# ESP32-Proto2-OSHPARK_Rev2.net
KiCad netlist of a schematic drawn in EAGLE
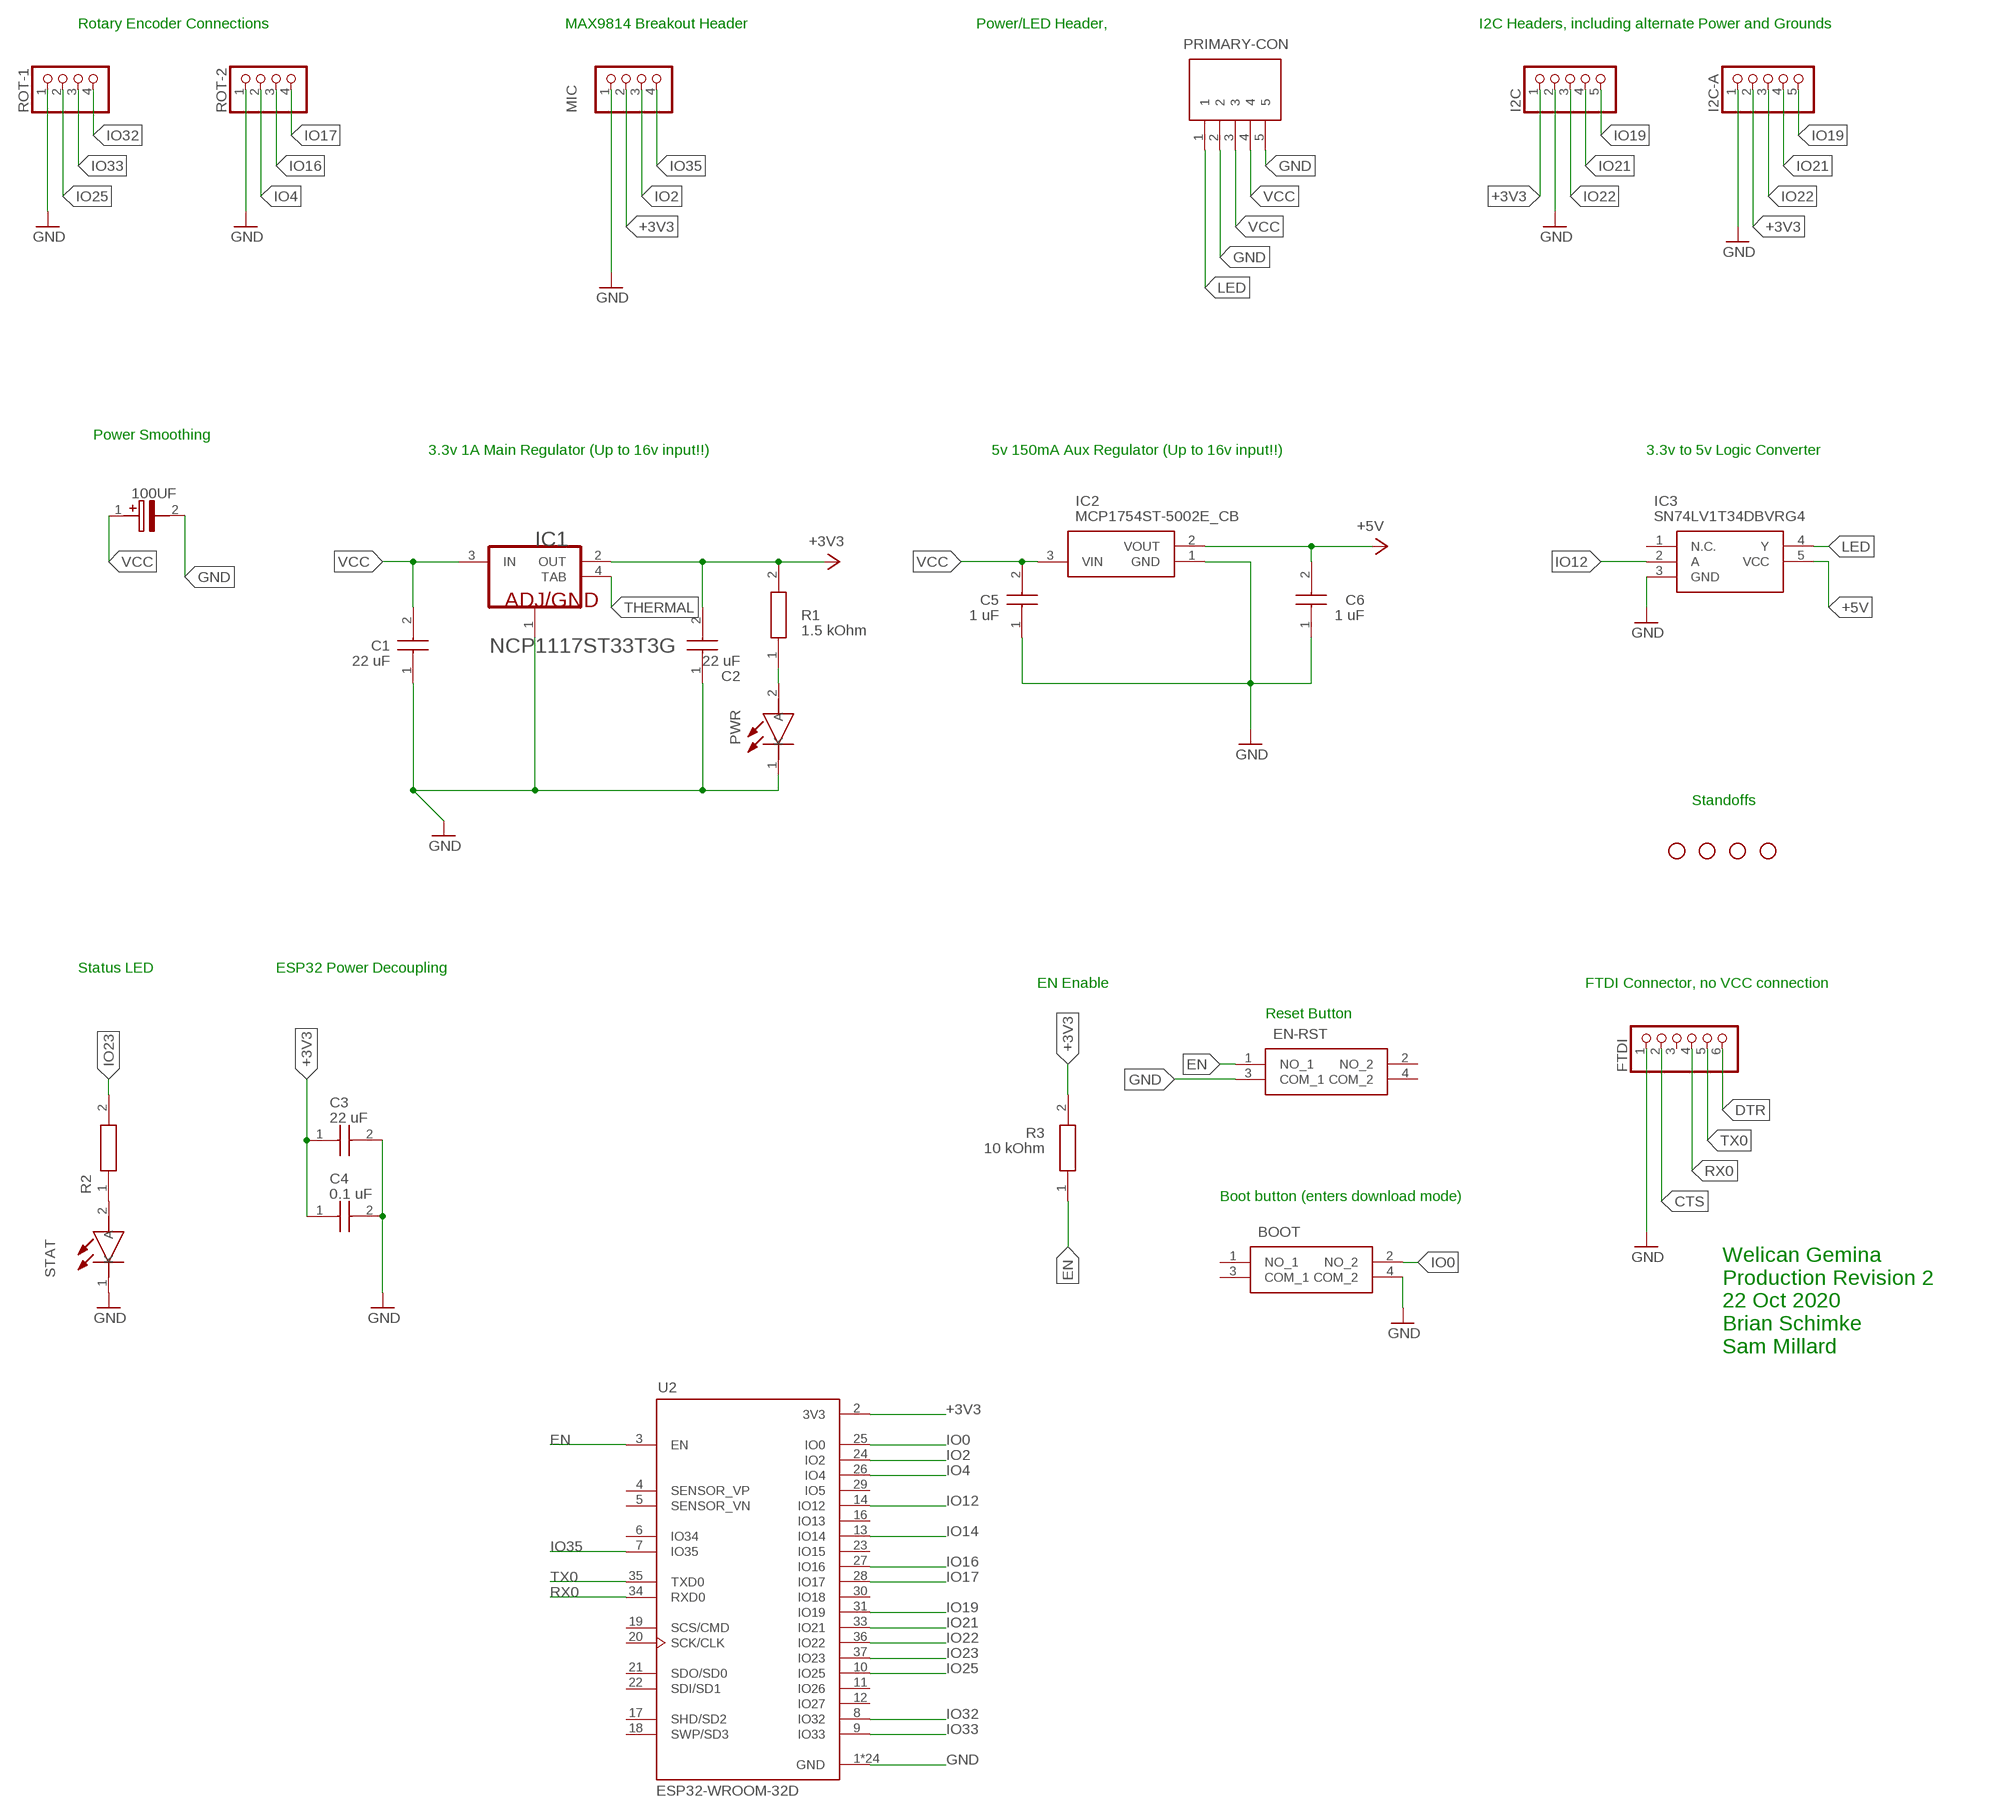
[diagram p0: schematic, sheet 1]

(export (version "E")
  (design (tool "Eeschema 10.0.6"))
  (components
    (comp (ref "100UF")
      (value "865080445010")
      (footprint "eagle-import:CAPAE660X770N")
      (fields (field (name "MOUSER_PART_NUMBER") "710-865080445010"))
      (libsource (lib "eagle-import") (part "865080445010"))
    )
    (comp (ref "BOOT")
      (value "PTS647SK70SMTR2LFS")
      (footprint "eagle-import:PTS647SK70SMTR2LFS")
      (fields (field (name "MOUSER_PART_NUMBER") "611-PTS647SK70SMTR2L"))
      (libsource (lib "eagle-import") (part "PTS647SK70SMTR2LFS"))
    )
    (comp (ref "C1")
      (value "22 uF")
      (footprint "eagle-import:CAPC3216X180N")
      (fields
        (field (name "MANUFACTURER_PART_NUMBER") "C1206C226M4PACTU")
        (field (name "MOUSER_PART_NUMBER") "80-C1206C226M4P")
      )
      (libsource (lib "eagle-import") (part "C1206C226M4PACTU"))
    )
    (comp (ref "C2")
      (value "22 uF")
      (footprint "eagle-import:CAPC3216X180N")
      (fields
        (field (name "MANUFACTURER_PART_NUMBER") "C1206C226M4PACTU")
        (field (name "MOUSER_PART_NUMBER") "80-C1206C226M4P")
      )
      (libsource (lib "eagle-import") (part "C1206C226M4PACTU"))
    )
    (comp (ref "C3")
      (value "22 uF")
      (footprint "eagle-import:CAPC3216X180N")
      (fields
        (field (name "MANUFACTURER_PART_NUMBER") "C1206C226M4PACTU")
        (field (name "MOUSER_PART_NUMBER") "80-C1206C226M4P")
      )
      (libsource (lib "eagle-import") (part "C1206C226M4PACTU"))
    )
    (comp (ref "C4")
      (value "0.1 uF")
      (footprint "eagle-import:CAPC3216X180N")
      (fields
        (field (name "MANUFACTURER_PART_NUMBER") "C1206C226M4PACTU")
        (field (name "MOUSER_PART_NUMBER") "80-C1206C226M4P")
      )
      (libsource (lib "eagle-import") (part "C1206C226M4PACTU"))
    )
    (comp (ref "C5")
      (value "1 uF")
      (footprint "eagle-import:CAPC3216X180N")
      (fields
        (field (name "MANUFACTURER_PART_NUMBER") "C1206C226M4PACTU")
        (field (name "MOUSER_PART_NUMBER") "80-C1206C226M4P")
      )
      (libsource (lib "eagle-import") (part "C1206C226M4PACTU"))
    )
    (comp (ref "C6")
      (value "1 uF")
      (footprint "eagle-import:CAPC3216X180N")
      (fields
        (field (name "MANUFACTURER_PART_NUMBER") "C1206C226M4PACTU")
        (field (name "MOUSER_PART_NUMBER") "80-C1206C226M4P")
      )
      (libsource (lib "eagle-import") (part "C1206C226M4PACTU"))
    )
    (comp (ref "EN-RST")
      (value "PTS647SK70SMTR2LFS")
      (footprint "eagle-import:PTS647SK70SMTR2LFS")
      (fields (field (name "MOUSER_PART_NUMBER") "611-PTS647SK70SMTR2L"))
      (libsource (lib "eagle-import") (part "PTS647SK70SMTR2LFS"))
    )
    (comp (ref "FTDI")
      (value "PINHD-1X6")
      (footprint "eagle-import:1X06")
      (libsource (lib "eagle-import") (part "PINHD-1X6"))
    )
    (comp (ref "H1")
      (value "STAND-OFF")
      (footprint "eagle-import:STAND-OFF")
      (libsource (lib "eagle-import") (part "STAND-OFF"))
    )
    (comp (ref "H2")
      (value "STAND-OFF")
      (footprint "eagle-import:STAND-OFF")
      (libsource (lib "eagle-import") (part "STAND-OFF"))
    )
    (comp (ref "H3")
      (value "STAND-OFF")
      (footprint "eagle-import:STAND-OFF")
      (libsource (lib "eagle-import") (part "STAND-OFF"))
    )
    (comp (ref "H4")
      (value "STAND-OFF")
      (footprint "eagle-import:STAND-OFF")
      (libsource (lib "eagle-import") (part "STAND-OFF"))
    )
    (comp (ref "I2C")
      (value "PINHD-1X5")
      (footprint "eagle-import:1X05")
      (libsource (lib "eagle-import") (part "PINHD-1X5"))
    )
    (comp (ref "I2C-A")
      (value "PINHD-1X5")
      (footprint "eagle-import:1X05")
      (libsource (lib "eagle-import") (part "PINHD-1X5"))
    )
    (comp (ref "IC1")
      (value "ON_SEMICONDUCTOR_NCP1117ST33T3GON_SEMICONDUCTOR_NCP1117ST33T3G_0_0")
      (footprint "eagle-import:ON_SEMICONDUCTOR_NCP1117ST33T3G_0")
      (fields
        (field (name "MF") "ON Semiconductor")
        (field (name "MPN") "NCP1117ST33T3G")
        (field (name "TOLERANCE") "1%")
      )
      (libsource (lib "eagle-import") (part "ON_SEMICONDUCTOR_NCP1117ST33T3GON_SEMICONDUCTOR_NCP1117ST33T3G_0_0"))
    )
    (comp (ref "IC2")
      (value "MCP1754ST-5002E_CB")
      (footprint "eagle-import:SOT95P255X145-3N")
      (fields
        (field (name "MANUFACTURER_PART_NUMBER") "MCP1754ST-5002E/CB")
        (field (name "MOUSER_PART_NUMBER") "579-MCP1754T-5002ECB")
      )
      (libsource (lib "eagle-import") (part "MCP1754ST-5002E_CB"))
    )
    (comp (ref "IC3")
      (value "SN74LV1T34DBVRG4")
      (footprint "eagle-import:SOT95P280X145-5N")
      (fields (field (name "MOUSER_PART_NUMBER") "595-SN74LV1T34DBVRG4"))
      (libsource (lib "eagle-import") (part "SN74LV1T34DBVRG4"))
    )
    (comp (ref "MIC")
      (value "PINHD-1X4")
      (footprint "eagle-import:1X04")
      (libsource (lib "eagle-import") (part "PINHD-1X4"))
    )
    (comp (ref "PRIMARY-CON")
      (value "1984646")
      (footprint "eagle-import:1984646")
      (libsource (lib "eagle-import") (part "1984646"))
    )
    (comp (ref "PWR")
      (value "150120AS75000")
      (footprint "eagle-import:LEDSC320X160X78-2N")
      (fields (field (name "MOUSER_PART_NUMBER") "710-150120AS75000"))
      (libsource (lib "eagle-import") (part "150120AS75000"))
    )
    (comp (ref "R1")
      (value "1.5 kOhm")
      (footprint "eagle-import:RESC3216X60N")
      (fields
        (field (name "MANUFACTURER_PART_NUMBER") "CRCW12061K00FKEB")
        (field (name "MOUSER_PART_NUMBER") "71-CRCW12061K00FKEB")
      )
      (libsource (lib "eagle-import") (part "CRCW12061K00FKEB"))
    )
    (comp (ref "R2")
      (value "CRCW12061K00FKEB")
      (footprint "eagle-import:RESC3216X60N")
      (fields (field (name "MOUSER_PART_NUMBER") "71-CRCW12061K00FKEB"))
      (libsource (lib "eagle-import") (part "CRCW12061K00FKEB"))
    )
    (comp (ref "R3")
      (value "10 kOhm")
      (footprint "eagle-import:RESC3216X60N")
      (fields
        (field (name "MANUFACTURER_PART_NUMBER") "CRCW12061K00FKEB")
        (field (name "MOUSER_PART_NUMBER") "71-CRCW12061K00FKEB")
      )
      (libsource (lib "eagle-import") (part "CRCW12061K00FKEB"))
    )
    (comp (ref "ROT-1")
      (value "PINHD-1X4")
      (footprint "eagle-import:1X04")
      (libsource (lib "eagle-import") (part "PINHD-1X4"))
    )
    (comp (ref "ROT-2")
      (value "PINHD-1X4")
      (footprint "eagle-import:1X04")
      (libsource (lib "eagle-import") (part "PINHD-1X4"))
    )
    (comp (ref "STAT")
      (value "150120AS75000")
      (footprint "eagle-import:LEDSC320X160X78-2N")
      (fields (field (name "MOUSER_PART_NUMBER") "710-150120AS75000"))
      (libsource (lib "eagle-import") (part "150120AS75000"))
    )
    (comp (ref "U2")
      (value "ESP32-WROOM-32D")
      (footprint "eagle-import:MODULE_ESP32-WROOM-32D")
      (fields (field (name "MF") "Espressif Systems"))
      (libsource (lib "eagle-import") (part "ESP32-WROOM-32D"))
    )
  )
  (nets
    (net (code "1") (name "+3V3") (class "Default")
      (node (ref "C2") (pin "2") (pinfunction "2_2") (pintype "bidirectional"))
      (node (ref "C3") (pin "1") (pinfunction "1_1") (pintype "bidirectional"))
      (node (ref "C4") (pin "1") (pinfunction "1_1") (pintype "bidirectional"))
      (node (ref "I2C") (pin "1") (pinfunction "1_1") (pintype "passive"))
      (node (ref "I2C-A") (pin "2") (pinfunction "2_2") (pintype "passive"))
      (node (ref "IC1") (pin "2") (pinfunction "OUT_2") (pintype "power_in"))
      (node (ref "MIC") (pin "2") (pinfunction "2_2") (pintype "passive"))
      (node (ref "R1") (pin "2") (pinfunction "2_2") (pintype "bidirectional"))
      (node (ref "R3") (pin "2") (pinfunction "2_2") (pintype "bidirectional"))
      (node (ref "U2") (pin "2") (pinfunction "3V3_2") (pintype "power_in"))
    )
    (net (code "2") (name "+5V") (class "Default")
      (node (ref "C6") (pin "2") (pinfunction "2_2") (pintype "bidirectional"))
      (node (ref "IC2") (pin "2") (pinfunction "VOUT_2") (pintype "bidirectional"))
      (node (ref "IC3") (pin "5") (pinfunction "VCC_5") (pintype "bidirectional"))
    )
    (net (code "3") (name "/IO14") (class "Default")
      (node (ref "U2") (pin "13") (pinfunction "IO14_13") (pintype "bidirectional"))
    )
    (net (code "4") (name "CTS") (class "Default")
      (node (ref "FTDI") (pin "2") (pinfunction "2_2") (pintype "passive"))
    )
    (net (code "5") (name "DTR") (class "Default")
      (node (ref "FTDI") (pin "6") (pinfunction "6_6") (pintype "passive"))
    )
    (net (code "6") (name "EN") (class "Default")
      (node (ref "EN-RST") (pin "1") (pinfunction "NO_1_1") (pintype "bidirectional"))
      (node (ref "R3") (pin "1") (pinfunction "1_1") (pintype "bidirectional"))
      (node (ref "U2") (pin "3") (pinfunction "EN_3") (pintype "input"))
    )
    (net (code "7") (name "GND") (class "Default")
      (node (ref "100UF") (pin "2") (pinfunction "-_2") (pintype "bidirectional"))
      (node (ref "BOOT") (pin "4") (pinfunction "COM_2_4") (pintype "bidirectional"))
      (node (ref "C1") (pin "1") (pinfunction "1_1") (pintype "bidirectional"))
      (node (ref "C2") (pin "1") (pinfunction "1_1") (pintype "bidirectional"))
      (node (ref "C3") (pin "2") (pinfunction "2_2") (pintype "bidirectional"))
      (node (ref "C4") (pin "2") (pinfunction "2_2") (pintype "bidirectional"))
      (node (ref "C5") (pin "1") (pinfunction "1_1") (pintype "bidirectional"))
      (node (ref "C6") (pin "1") (pinfunction "1_1") (pintype "bidirectional"))
      (node (ref "EN-RST") (pin "3") (pinfunction "COM_1_3") (pintype "bidirectional"))
      (node (ref "FTDI") (pin "1") (pinfunction "1_1") (pintype "passive"))
      (node (ref "I2C") (pin "2") (pinfunction "2_2") (pintype "passive"))
      (node (ref "I2C-A") (pin "1") (pinfunction "1_1") (pintype "passive"))
      (node (ref "IC1") (pin "1") (pinfunction "ADJ/GND_1") (pintype "passive"))
      (node (ref "IC2") (pin "1") (pinfunction "GND_1") (pintype "bidirectional"))
      (node (ref "IC3") (pin "3") (pinfunction "GND_3") (pintype "bidirectional"))
      (node (ref "MIC") (pin "1") (pinfunction "1_1") (pintype "passive"))
      (node (ref "PRIMARY-CON") (pin "2") (pinfunction "2_2") (pintype "bidirectional"))
      (node (ref "PRIMARY-CON") (pin "5") (pinfunction "5_5") (pintype "bidirectional"))
      (node (ref "PWR") (pin "1") (pinfunction "K_1") (pintype "bidirectional"))
      (node (ref "ROT-1") (pin "1") (pinfunction "1_1") (pintype "passive"))
      (node (ref "ROT-2") (pin "1") (pinfunction "1_1") (pintype "passive"))
      (node (ref "STAT") (pin "1") (pinfunction "K_1") (pintype "bidirectional"))
      (node (ref "U2") (pin "1") (pinfunction "GND_1") (pintype "power_in"))
      (node (ref "U2") (pin "15") (pinfunction "GND_15") (pintype "power_in"))
      (node (ref "U2") (pin "38") (pinfunction "GND_38") (pintype "power_in"))
      (node (ref "U2") (pin "39_1") (pinfunction "GND_39_1") (pintype "power_in"))
      (node (ref "U2") (pin "39_10") (pinfunction "GND_39_10") (pintype "power_in"))
      (node (ref "U2") (pin "39_11") (pinfunction "GND_39_11") (pintype "power_in"))
      (node (ref "U2") (pin "39_12") (pinfunction "GND_39_12") (pintype "power_in"))
      (node (ref "U2") (pin "39_13") (pinfunction "GND_39_13") (pintype "power_in"))
      (node (ref "U2") (pin "39_14") (pinfunction "GND_39_14") (pintype "power_in"))
      (node (ref "U2") (pin "39_15") (pinfunction "GND_39_15") (pintype "power_in"))
      (node (ref "U2") (pin "39_16") (pinfunction "GND_39_16") (pintype "power_in"))
      (node (ref "U2") (pin "39_17") (pinfunction "GND_39_17") (pintype "power_in"))
      (node (ref "U2") (pin "39_18") (pinfunction "GND_39_18") (pintype "power_in"))
      (node (ref "U2") (pin "39_19") (pinfunction "GND_39_19") (pintype "power_in"))
      (node (ref "U2") (pin "39_2") (pinfunction "GND_39_2") (pintype "power_in"))
      (node (ref "U2") (pin "39_20") (pinfunction "GND_39_20") (pintype "power_in"))
      (node (ref "U2") (pin "39_21") (pinfunction "GND_39_21") (pintype "power_in"))
      (node (ref "U2") (pin "39_3") (pinfunction "GND_39_3") (pintype "power_in"))
      (node (ref "U2") (pin "39_4") (pinfunction "GND_39_4") (pintype "power_in"))
      (node (ref "U2") (pin "39_5") (pinfunction "GND_39_5") (pintype "power_in"))
      (node (ref "U2") (pin "39_6") (pinfunction "GND_39_6") (pintype "power_in"))
      (node (ref "U2") (pin "39_7") (pinfunction "GND_39_7") (pintype "power_in"))
      (node (ref "U2") (pin "39_8") (pinfunction "GND_39_8") (pintype "power_in"))
      (node (ref "U2") (pin "39_9") (pinfunction "GND_39_9") (pintype "power_in"))
    )
    (net (code "8") (name "IO0") (class "Default")
      (node (ref "BOOT") (pin "2") (pinfunction "NO_2_2") (pintype "bidirectional"))
      (node (ref "U2") (pin "25") (pinfunction "IO0_25") (pintype "bidirectional"))
    )
    (net (code "9") (name "IO2") (class "Default")
      (node (ref "MIC") (pin "3") (pinfunction "3_3") (pintype "passive"))
      (node (ref "U2") (pin "24") (pinfunction "IO2_24") (pintype "bidirectional"))
    )
    (net (code "10") (name "IO4") (class "Default")
      (node (ref "ROT-2") (pin "2") (pinfunction "2_2") (pintype "passive"))
      (node (ref "U2") (pin "26") (pinfunction "IO4_26") (pintype "bidirectional"))
    )
    (net (code "11") (name "IO12") (class "Default")
      (node (ref "IC3") (pin "2") (pinfunction "A_2") (pintype "bidirectional"))
      (node (ref "U2") (pin "14") (pinfunction "IO12_14") (pintype "bidirectional"))
    )
    (net (code "12") (name "IO16") (class "Default")
      (node (ref "ROT-2") (pin "3") (pinfunction "3_3") (pintype "passive"))
      (node (ref "U2") (pin "27") (pinfunction "IO16_27") (pintype "bidirectional"))
    )
    (net (code "13") (name "IO17") (class "Default")
      (node (ref "ROT-2") (pin "4") (pinfunction "4_4") (pintype "passive"))
      (node (ref "U2") (pin "28") (pinfunction "IO17_28") (pintype "bidirectional"))
    )
    (net (code "14") (name "IO19") (class "Default")
      (node (ref "I2C") (pin "5") (pinfunction "5_5") (pintype "passive"))
      (node (ref "I2C-A") (pin "5") (pinfunction "5_5") (pintype "passive"))
      (node (ref "U2") (pin "31") (pinfunction "IO19_31") (pintype "bidirectional"))
    )
    (net (code "15") (name "IO21") (class "Default")
      (node (ref "I2C") (pin "4") (pinfunction "4_4") (pintype "passive"))
      (node (ref "I2C-A") (pin "4") (pinfunction "4_4") (pintype "passive"))
      (node (ref "U2") (pin "33") (pinfunction "IO21_33") (pintype "bidirectional"))
    )
    (net (code "16") (name "IO22") (class "Default")
      (node (ref "I2C") (pin "3") (pinfunction "3_3") (pintype "passive"))
      (node (ref "I2C-A") (pin "3") (pinfunction "3_3") (pintype "passive"))
      (node (ref "U2") (pin "36") (pinfunction "IO22_36") (pintype "bidirectional"))
    )
    (net (code "17") (name "IO23") (class "Default")
      (node (ref "R2") (pin "2") (pinfunction "2_2") (pintype "bidirectional"))
      (node (ref "U2") (pin "37") (pinfunction "IO23_37") (pintype "bidirectional"))
    )
    (net (code "18") (name "IO25") (class "Default")
      (node (ref "ROT-1") (pin "2") (pinfunction "2_2") (pintype "passive"))
      (node (ref "U2") (pin "10") (pinfunction "IO25_10") (pintype "bidirectional"))
    )
    (net (code "19") (name "IO32") (class "Default")
      (node (ref "ROT-1") (pin "4") (pinfunction "4_4") (pintype "passive"))
      (node (ref "U2") (pin "8") (pinfunction "IO32_8") (pintype "bidirectional"))
    )
    (net (code "20") (name "IO33") (class "Default")
      (node (ref "ROT-1") (pin "3") (pinfunction "3_3") (pintype "passive"))
      (node (ref "U2") (pin "9") (pinfunction "IO33_9") (pintype "bidirectional"))
    )
    (net (code "21") (name "IO35") (class "Default")
      (node (ref "MIC") (pin "4") (pinfunction "4_4") (pintype "passive"))
      (node (ref "U2") (pin "7") (pinfunction "IO35_7") (pintype "input"))
    )
    (net (code "22") (name "LED") (class "Default")
      (node (ref "IC3") (pin "4") (pinfunction "Y_4") (pintype "bidirectional"))
      (node (ref "PRIMARY-CON") (pin "1") (pinfunction "1_1") (pintype "bidirectional"))
    )
    (net (code "23") (name "Net-(PWR-A)") (class "Default")
      (node (ref "PWR") (pin "2") (pinfunction "A_2") (pintype "bidirectional"))
      (node (ref "R1") (pin "1") (pinfunction "1_1") (pintype "bidirectional"))
    )
    (net (code "24") (name "Net-(STAT-A)") (class "Default")
      (node (ref "R2") (pin "1") (pinfunction "1_1") (pintype "bidirectional"))
      (node (ref "STAT") (pin "2") (pinfunction "A_2") (pintype "bidirectional"))
    )
    (net (code "25") (name "RX0") (class "Default")
      (node (ref "FTDI") (pin "4") (pinfunction "4_4") (pintype "passive"))
      (node (ref "U2") (pin "34") (pinfunction "RXD0_34") (pintype "bidirectional"))
    )
    (net (code "26") (name "THERMAL") (class "Default")
      (node (ref "IC1") (pin "4") (pinfunction "TAB_4") (pintype "passive"))
    )
    (net (code "27") (name "TX0") (class "Default")
      (node (ref "FTDI") (pin "5") (pinfunction "5_5") (pintype "passive"))
      (node (ref "U2") (pin "35") (pinfunction "TXD0_35") (pintype "bidirectional"))
    )
    (net (code "28") (name "VCC") (class "Default")
      (node (ref "100UF") (pin "1") (pinfunction "+_1") (pintype "bidirectional"))
      (node (ref "C1") (pin "2") (pinfunction "2_2") (pintype "bidirectional"))
      (node (ref "C5") (pin "2") (pinfunction "2_2") (pintype "bidirectional"))
      (node (ref "IC1") (pin "3") (pinfunction "IN_3") (pintype "power_in"))
      (node (ref "IC2") (pin "3") (pinfunction "VIN_3") (pintype "bidirectional"))
      (node (ref "PRIMARY-CON") (pin "3") (pinfunction "3_3") (pintype "bidirectional"))
      (node (ref "PRIMARY-CON") (pin "4") (pinfunction "4_4") (pintype "bidirectional"))
    )
    (net (code "29") (name "unconnected-(BOOT-COM_1-Pad3)") (class "Default")
      (node (ref "BOOT") (pin "3") (pinfunction "COM_1_3") (pintype "bidirectional"))
    )
    (net (code "30") (name "unconnected-(BOOT-NO_1-Pad1)") (class "Default")
      (node (ref "BOOT") (pin "1") (pinfunction "NO_1_1") (pintype "bidirectional"))
    )
    (net (code "31") (name "unconnected-(EN-RST-COM_2-Pad4)") (class "Default")
      (node (ref "EN-RST") (pin "4") (pinfunction "COM_2_4") (pintype "bidirectional"))
    )
    (net (code "32") (name "unconnected-(EN-RST-NO_2-Pad2)") (class "Default")
      (node (ref "EN-RST") (pin "2") (pinfunction "NO_2_2") (pintype "bidirectional"))
    )
    (net (code "33") (name "unconnected-(FTDI-Pad3)") (class "Default")
      (node (ref "FTDI") (pin "3") (pinfunction "3_3") (pintype "passive"))
    )
    (net (code "34") (name "unconnected-(IC3-N.C.-Pad1)") (class "Default")
      (node (ref "IC3") (pin "1") (pinfunction "N.C._1") (pintype "no_connect"))
    )
    (net (code "35") (name "unconnected-(U2-IO5-Pad29)") (class "Default")
      (node (ref "U2") (pin "29") (pinfunction "IO5_29") (pintype "bidirectional"))
    )
    (net (code "36") (name "unconnected-(U2-IO13-Pad16)") (class "Default")
      (node (ref "U2") (pin "16") (pinfunction "IO13_16") (pintype "bidirectional"))
    )
    (net (code "37") (name "unconnected-(U2-IO15-Pad23)") (class "Default")
      (node (ref "U2") (pin "23") (pinfunction "IO15_23") (pintype "bidirectional"))
    )
    (net (code "38") (name "unconnected-(U2-IO18-Pad30)") (class "Default")
      (node (ref "U2") (pin "30") (pinfunction "IO18_30") (pintype "bidirectional"))
    )
    (net (code "39") (name "unconnected-(U2-IO26-Pad11)") (class "Default")
      (node (ref "U2") (pin "11") (pinfunction "IO26_11") (pintype "bidirectional"))
    )
    (net (code "40") (name "unconnected-(U2-IO27-Pad12)") (class "Default")
      (node (ref "U2") (pin "12") (pinfunction "IO27_12") (pintype "bidirectional"))
    )
    (net (code "41") (name "unconnected-(U2-IO34-Pad6)") (class "Default")
      (node (ref "U2") (pin "6") (pinfunction "IO34_6") (pintype "input"))
    )
    (net (code "42") (name "unconnected-(U2-SCK{slash}CLK-Pad20)") (class "Default")
      (node (ref "U2") (pin "20") (pinfunction "SCK/CLK_20") (pintype "bidirectional"))
    )
    (net (code "43") (name "unconnected-(U2-SCS{slash}CMD-Pad19)") (class "Default")
      (node (ref "U2") (pin "19") (pinfunction "SCS/CMD_19") (pintype "bidirectional"))
    )
    (net (code "44") (name "unconnected-(U2-SDI{slash}SD1-Pad22)") (class "Default")
      (node (ref "U2") (pin "22") (pinfunction "SDI/SD1_22") (pintype "bidirectional"))
    )
    (net (code "45") (name "unconnected-(U2-SDO{slash}SD0-Pad21)") (class "Default")
      (node (ref "U2") (pin "21") (pinfunction "SDO/SD0_21") (pintype "bidirectional"))
    )
    (net (code "46") (name "unconnected-(U2-SENSOR_VN-Pad5)") (class "Default")
      (node (ref "U2") (pin "5") (pinfunction "SENSOR_VN_5") (pintype "input"))
    )
    (net (code "47") (name "unconnected-(U2-SENSOR_VP-Pad4)") (class "Default")
      (node (ref "U2") (pin "4") (pinfunction "SENSOR_VP_4") (pintype "input"))
    )
    (net (code "48") (name "unconnected-(U2-SHD{slash}SD2-Pad17)") (class "Default")
      (node (ref "U2") (pin "17") (pinfunction "SHD/SD2_17") (pintype "bidirectional"))
    )
    (net (code "49") (name "unconnected-(U2-SWP{slash}SD3-Pad18)") (class "Default")
      (node (ref "U2") (pin "18") (pinfunction "SWP/SD3_18") (pintype "bidirectional"))
    )
  )
)
